# Orbit_PA_dev.net
KiCad netlist of a schematic drawn in Altium Designer
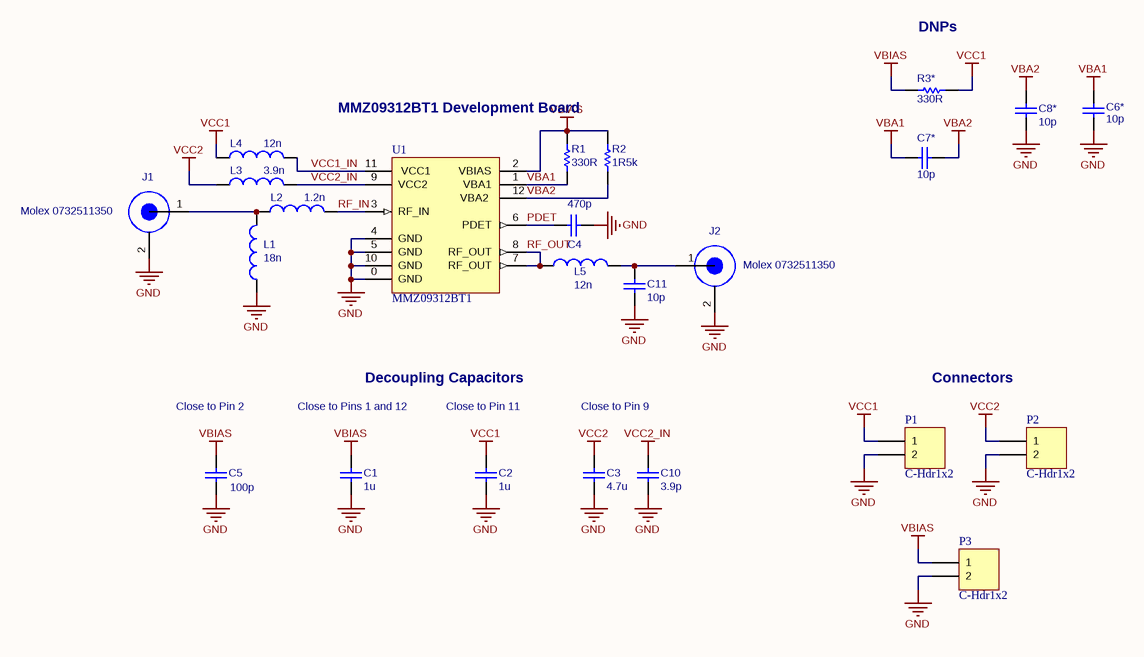
[diagram p0: Orbit_PA_dev.SchDoc]

(export (version "E")
  (design (tool "Eeschema 10.0.6"))
  (components
    (comp (ref "C1")
      (value "1u")
      (footprint "CAP 1005 (0402) B-Density")
      (description "Capacitor")
      (libsource (lib "orbit_PA") (part "CAPACITOR (GENERAL)"))
    )
    (comp (ref "C2")
      (value "1u")
      (footprint "CAP 1005 (0402) B-Density")
      (description "Capacitor")
      (libsource (lib "orbit_PA") (part "CAPACITOR (GENERAL)"))
    )
    (comp (ref "C3")
      (value "4.7u")
      (footprint "CAP 1608 (0603) B-Density")
      (description "Capacitor")
      (libsource (lib "orbit_PA") (part "CAPACITOR (GENERAL)"))
    )
    (comp (ref "C4")
      (value "470p")
      (footprint "CAP 1005 (0402) B-Density")
      (description "Capacitor")
      (libsource (lib "orbit_PA") (part "CAPACITOR (GENERAL)"))
    )
    (comp (ref "C5")
      (value "100p")
      (footprint "CAP 1005 (0402) B-Density")
      (description "Capacitor")
      (libsource (lib "orbit_PA") (part "CAPACITOR (GENERAL)"))
    )
    (comp (ref "C6*")
      (value "10p")
      (footprint "CAP 1005 (0402) B-Density")
      (description "Capacitor")
      (libsource (lib "orbit_PA") (part "CAPACITOR (GENERAL)"))
    )
    (comp (ref "C7*")
      (value "10p")
      (footprint "CAP 1005 (0402) B-Density")
      (description "Capacitor")
      (libsource (lib "orbit_PA") (part "CAPACITOR (GENERAL)"))
    )
    (comp (ref "C8*")
      (value "10p")
      (footprint "CAP 1005 (0402) B-Density")
      (description "Capacitor")
      (libsource (lib "orbit_PA") (part "CAPACITOR (GENERAL)"))
    )
    (comp (ref "C10")
      (value "3.9p")
      (footprint "CAP 1005 (0402) B-Density")
      (description "Capacitor")
      (libsource (lib "orbit_PA") (part "CAPACITOR (GENERAL)"))
    )
    (comp (ref "C11")
      (value "10p")
      (footprint "CAP 1005 (0402) B-Density")
      (description "Capacitor")
      (libsource (lib "orbit_PA") (part "CAPACITOR (GENERAL)"))
    )
    (comp (ref "J1")
      (value "Molex 0732511350")
      (footprint "MOLEX 732511350")
      (libsource (lib "orbit_PA") (part "SMA CONNECTOR (GENERAL)"))
    )
    (comp (ref "J2")
      (value "Molex 0732511350")
      (footprint "MOLEX 732511350")
      (libsource (lib "orbit_PA") (part "SMA CONNECTOR (GENERAL)"))
    )
    (comp (ref "L1")
      (value "18n")
      (footprint "IND 1608 (0603)")
      (description "Inductor")
      (libsource (lib "orbit_PA") (part "INDUCTOR (GENERAL)"))
    )
    (comp (ref "L2")
      (value "1.2n")
      (footprint "IND 1608 (0603)")
      (description "Inductor")
      (libsource (lib "orbit_PA") (part "INDUCTOR (GENERAL)"))
    )
    (comp (ref "L3")
      (value "3.9n")
      (footprint "IND 1608 (0603)")
      (description "Inductor")
      (libsource (lib "orbit_PA") (part "INDUCTOR (GENERAL)"))
    )
    (comp (ref "L4")
      (value "12n")
      (footprint "IND 1608 (0603)")
      (description "Inductor")
      (libsource (lib "orbit_PA") (part "INDUCTOR (GENERAL)"))
    )
    (comp (ref "L5")
      (value "12n")
      (footprint "IND 1608 (0603)")
      (description "Inductor")
      (libsource (lib "orbit_PA") (part "INDUCTOR (GENERAL)"))
    )
    (comp (ref "P1")
      (value "C-Hdr1x2")
      (footprint "HDR1X2_LGE1.0")
      (description "Header, 2-Pin")
      (fields (field (name "PUBLISHER") "Altium Limited"))
      (libsource (lib "orbit_PA") (part "C-Hdr1x2"))
    )
    (comp (ref "P2")
      (value "C-Hdr1x2")
      (footprint "HDR1X2_LGE1.0")
      (description "Header, 2-Pin")
      (fields (field (name "PUBLISHER") "Altium Limited"))
      (libsource (lib "orbit_PA") (part "C-Hdr1x2"))
    )
    (comp (ref "P3")
      (value "C-Hdr1x2")
      (footprint "HDR1X2_LGE1.0")
      (description "Header, 2-Pin")
      (fields (field (name "PUBLISHER") "Altium Limited"))
      (libsource (lib "orbit_PA") (part "C-Hdr1x2"))
    )
    (comp (ref "R1")
      (value "330R")
      (footprint "RES 1005 (0402)")
      (description "Resistor")
      (libsource (lib "orbit_PA") (part "RESISTOR (GENERAL)"))
    )
    (comp (ref "R2")
      (value "1R5k")
      (footprint "RES 1005 (0402)")
      (description "Resistor")
      (libsource (lib "orbit_PA") (part "RESISTOR (GENERAL)"))
    )
    (comp (ref "R3*")
      (value "330R")
      (footprint "RES 1005 (0402)")
      (description "Resistor")
      (libsource (lib "orbit_PA") (part "RESISTOR (GENERAL)"))
    )
    (comp (ref "U1")
      (value "MMZ09312BT1")
      (footprint "QFN 3x3")
      (description "IC RF AMP CDMA 400MHZ-1GHZ 12QFN")
      (libsource (lib "orbit_PA") (part "MMZ09312BT1"))
    )
  )
  (nets
    (net (code "1") (name "/PDET") (class "Default")
      (node (ref "C4") (pin "1") (pinfunction "1_1") (pintype "passive"))
      (node (ref "U1") (pin "6") (pinfunction "PDET_6") (pintype "output"))
    )
    (net (code "2") (name "/RF_IN") (class "Default")
      (node (ref "L2") (pin "2") (pinfunction "2_2") (pintype "passive"))
      (node (ref "U1") (pin "3") (pinfunction "RF_IN_3") (pintype "input"))
    )
    (net (code "3") (name "/RF_OUT") (class "Default")
      (node (ref "L5") (pin "1") (pinfunction "1_1") (pintype "passive"))
      (node (ref "U1") (pin "7") (pinfunction "RF_OUT_7") (pintype "output"))
      (node (ref "U1") (pin "8") (pinfunction "RF_OUT_8") (pintype "output"))
    )
    (net (code "4") (name "/VCC1_IN") (class "Default")
      (node (ref "L4") (pin "2") (pinfunction "2_2") (pintype "passive"))
      (node (ref "U1") (pin "11") (pinfunction "VCC1_11") (pintype "power_in"))
    )
    (net (code "5") (name "GND") (class "Default")
      (node (ref "C1") (pin "1") (pinfunction "1_1") (pintype "passive"))
      (node (ref "C10") (pin "1") (pinfunction "1_1") (pintype "passive"))
      (node (ref "C11") (pin "1") (pinfunction "1_1") (pintype "passive"))
      (node (ref "C2") (pin "1") (pinfunction "1_1") (pintype "passive"))
      (node (ref "C3") (pin "1") (pinfunction "1_1") (pintype "passive"))
      (node (ref "C4") (pin "2") (pinfunction "2_2") (pintype "passive"))
      (node (ref "C5") (pin "1") (pinfunction "1_1") (pintype "passive"))
      (node (ref "C6*") (pin "1") (pinfunction "1_1") (pintype "passive"))
      (node (ref "C8*") (pin "1") (pinfunction "1_1") (pintype "passive"))
      (node (ref "J1") (pin "2") (pintype "passive"))
      (node (ref "J2") (pin "2") (pintype "passive"))
      (node (ref "L1") (pin "1") (pinfunction "1_1") (pintype "passive"))
      (node (ref "P1") (pin "2") (pinfunction "2_2") (pintype "passive"))
      (node (ref "P2") (pin "2") (pinfunction "2_2") (pintype "passive"))
      (node (ref "P3") (pin "2") (pinfunction "2_2") (pintype "passive"))
      (node (ref "U1") (pin "0") (pinfunction "GND_0") (pintype "passive"))
      (node (ref "U1") (pin "10") (pinfunction "GND_10") (pintype "passive"))
      (node (ref "U1") (pin "4") (pinfunction "GND_4") (pintype "passive"))
      (node (ref "U1") (pin "5") (pinfunction "GND_5") (pintype "passive"))
    )
    (net (code "6") (name "Net-(C11-Pad2)") (class "Default")
      (node (ref "C11") (pin "2") (pinfunction "2_2") (pintype "passive"))
      (node (ref "J2") (pin "1") (pintype "passive"))
      (node (ref "L5") (pin "2") (pinfunction "2_2") (pintype "passive"))
    )
    (net (code "7") (name "Net-(J1-Pad1)") (class "Default")
      (node (ref "J1") (pin "1") (pintype "passive"))
      (node (ref "L1") (pin "2") (pinfunction "2_2") (pintype "passive"))
      (node (ref "L2") (pin "1") (pinfunction "1_1") (pintype "passive"))
    )
    (net (code "8") (name "VBA1") (class "Default")
      (node (ref "C6*") (pin "2") (pinfunction "2_2") (pintype "passive"))
      (node (ref "C7*") (pin "2") (pinfunction "2_2") (pintype "passive"))
      (node (ref "R1") (pin "1") (pinfunction "1_1") (pintype "passive"))
      (node (ref "U1") (pin "1") (pinfunction "VBA1_1") (pintype "power_in"))
    )
    (net (code "9") (name "VBA2") (class "Default")
      (node (ref "C7*") (pin "1") (pinfunction "1_1") (pintype "passive"))
      (node (ref "C8*") (pin "2") (pinfunction "2_2") (pintype "passive"))
      (node (ref "R2") (pin "1") (pinfunction "1_1") (pintype "passive"))
      (node (ref "U1") (pin "12") (pinfunction "VBA2_12") (pintype "power_in"))
    )
    (net (code "10") (name "VBIAS") (class "Default")
      (node (ref "C1") (pin "2") (pinfunction "2_2") (pintype "passive"))
      (node (ref "C5") (pin "2") (pinfunction "2_2") (pintype "passive"))
      (node (ref "P3") (pin "1") (pinfunction "1_1") (pintype "passive"))
      (node (ref "R1") (pin "2") (pinfunction "2_2") (pintype "passive"))
      (node (ref "R2") (pin "2") (pinfunction "2_2") (pintype "passive"))
      (node (ref "R3*") (pin "2") (pinfunction "2_2") (pintype "passive"))
      (node (ref "U1") (pin "2") (pinfunction "VBIAS_2") (pintype "power_in"))
    )
    (net (code "11") (name "VCC1") (class "Default")
      (node (ref "C2") (pin "2") (pinfunction "2_2") (pintype "passive"))
      (node (ref "L4") (pin "1") (pinfunction "1_1") (pintype "passive"))
      (node (ref "P1") (pin "1") (pinfunction "1_1") (pintype "passive"))
      (node (ref "R3*") (pin "1") (pinfunction "1_1") (pintype "passive"))
    )
    (net (code "12") (name "VCC2") (class "Default")
      (node (ref "C3") (pin "2") (pinfunction "2_2") (pintype "passive"))
      (node (ref "L3") (pin "1") (pinfunction "1_1") (pintype "passive"))
      (node (ref "P2") (pin "1") (pinfunction "1_1") (pintype "passive"))
    )
    (net (code "13") (name "VCC2_IN") (class "Default")
      (node (ref "C10") (pin "2") (pinfunction "2_2") (pintype "passive"))
      (node (ref "L3") (pin "2") (pinfunction "2_2") (pintype "passive"))
      (node (ref "U1") (pin "9") (pinfunction "VCC2_9") (pintype "power_in"))
    )
  )
)
